# MLX90393SLW.net
KiCad netlist of a schematic drawn in Altium Designer
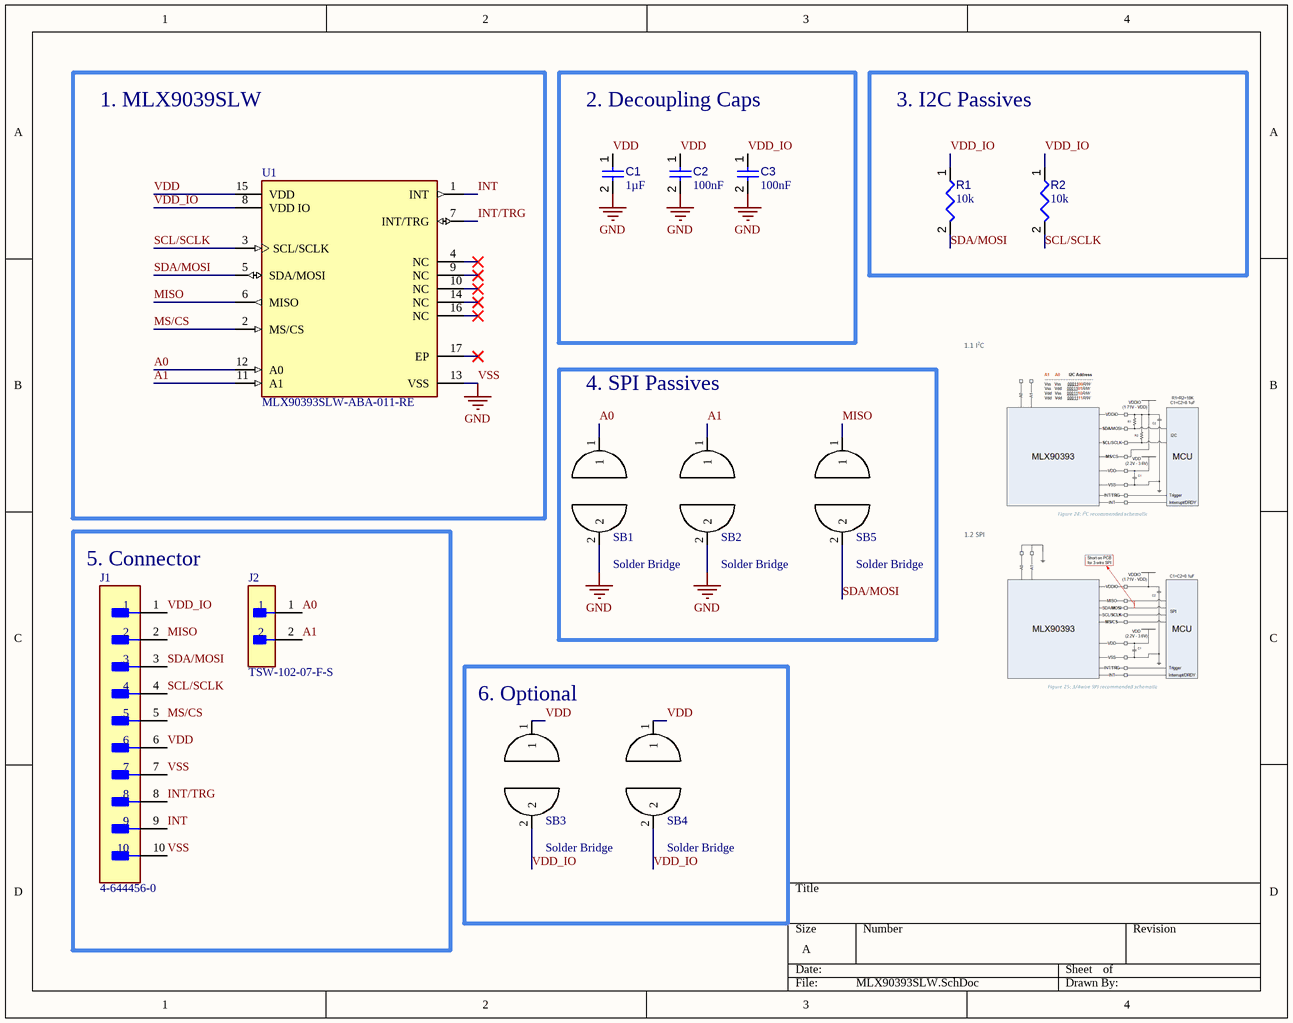
[diagram p0: MLX90393SLW.SchDoc]

(export (version "E")
  (design (tool "Eeschema 10.0.6"))
  (components
    (comp (ref "C1")
      (value "1µF")
      (footprint "CAPC0402(1005)60_L")
      (description "Chip Capacitor, 1µF +/-20%, 10V, 0402, Thickness 0.6 mm")
      (fields (field (name "TOLERANCE") "10%") (field (name "Comment") "Capacitor 1µF +/-20% 10V 0402"))
      (libsource (lib "SUBC") (part "CAP-NP-2"))
    )
    (comp (ref "C2")
      (value "100nF")
      (footprint "CAPC0402(1005)60_L")
      (description "Chip Capacitor, 100nF +/-20%, 25V, 0402, Thickness 0.6 mm")
      (fields (field (name "TOLERANCE") "10%") (field (name "Comment") "Capacitor 100nF +/-20% 25V 0402"))
      (libsource (lib "SUBC") (part "CAP-NP-2"))
    )
    (comp (ref "C3")
      (value "100nF")
      (footprint "CAPC0402(1005)60_L")
      (description "Chip Capacitor, 100nF +/-20%, 25V, 0402, Thickness 0.6 mm")
      (fields (field (name "TOLERANCE") "10%") (field (name "Comment") "Capacitor 100nF +/-20% 25V 0402"))
      (libsource (lib "SUBC") (part "CAP-NP-2"))
    )
    (comp (ref "J1")
      (value "4-644456-0")
      (footprint "FP-4-644456-0-MFG")
      (description "Conn Unshrouded Header HDR 10 POS 2.54mm Solder ST Top Entry Thru-Hole Bag/Box")
      (libsource (lib "SUBC") (part "aee40dc8b284c03a16094555aa210be"))
    )
    (comp (ref "J2")
      (value "TSW-102-07-F-S")
      (footprint "FP-TSW-102-07-F-S-MFG")
      (description "Conn Unshrouded Header HDR 2 POS 2.54mm Solder ST Top Entry Thru-Hole Bag")
      (libsource (lib "SUBC") (part "3bc925449376181038e59eaffc5286c"))
    )
    (comp (ref "R1")
      (value "10k")
      (footprint "RESC1608X55X25ML10T15")
      (description "Chip Resistor, 10 KOhm, +/- 1%, 01 W, -55 to 155 degC, 0603 (1608 Metric)")
      (fields (field (name "POWER") "100mW") (field (name "TOLERANCE") "1%"))
      (libsource (lib "SUBC") (part "RES-2"))
    )
    (comp (ref "R2")
      (value "10k")
      (footprint "RESC1608X55X25ML10T15")
      (description "Chip Resistor, 10 KOhm, +/- 1%, 01 W, -55 to 155 degC, 0603 (1608 Metric)")
      (fields (field (name "POWER") "100mW") (field (name "TOLERANCE") "1%"))
      (libsource (lib "SUBC") (part "RES-2"))
    )
    (comp (ref "SB1")
      (value "Solder Bridge")
      (footprint "Solder Bridge-Footprint-1")
      (description "Solder Bridge 10mil gap 6mil short")
      (libsource (lib "SUBC") (part "Solder Bridge-Symbol-1"))
    )
    (comp (ref "SB2")
      (value "Solder Bridge")
      (footprint "Solder Bridge-Footprint-1")
      (description "Solder Bridge 10mil gap 6mil short")
      (libsource (lib "SUBC") (part "Solder Bridge-Symbol-1"))
    )
    (comp (ref "SB3")
      (value "Solder Bridge")
      (footprint "Solder Bridge-Footprint-1")
      (description "Solder Bridge 10mil gap 6mil short")
      (libsource (lib "SUBC") (part "Solder Bridge-Symbol-1"))
    )
    (comp (ref "SB4")
      (value "Solder Bridge")
      (footprint "Solder Bridge-Footprint-1")
      (description "Solder Bridge 10mil gap 6mil short")
      (libsource (lib "SUBC") (part "Solder Bridge-Symbol-1"))
    )
    (comp (ref "SB5")
      (value "Solder Bridge")
      (footprint "Solder Bridge-Footprint-1")
      (description "Solder Bridge 10mil gap 6mil short")
      (libsource (lib "SUBC") (part "Solder Bridge-Symbol-1"))
    )
    (comp (ref "U1")
      (value "MLX90393SLW-ABA-011-RE")
      (footprint "FP-MLX90393SLW-ABA-011-RE-IPC_B")
      (description "Triaxis® Magnetic node - Micropower Magnetometer ft. SPI/I2C Output - I2C_addres")
      (libsource (lib "SUBC") (part "7beef37ec6f4d1a785de8af668c35a3"))
    )
  )
  (nets
    (net (code "1") (name "/A0") (class "Default")
      (node (ref "J2") (pin "1") (pinfunction "1_1") (pintype "passive"))
      (node (ref "SB1") (pin "1") (pinfunction "1_1") (pintype "passive"))
      (node (ref "U1") (pin "12") (pinfunction "A0_12") (pintype "input"))
    )
    (net (code "2") (name "/A1") (class "Default")
      (node (ref "J2") (pin "2") (pinfunction "2_2") (pintype "passive"))
      (node (ref "SB2") (pin "1") (pinfunction "1_1") (pintype "passive"))
      (node (ref "U1") (pin "11") (pinfunction "A1_11") (pintype "input"))
    )
    (net (code "3") (name "/INT") (class "Default")
      (node (ref "J1") (pin "9") (pinfunction "9_9") (pintype "passive"))
      (node (ref "U1") (pin "1") (pinfunction "INT_1") (pintype "output"))
    )
    (net (code "4") (name "/INT{slash}TRG") (class "Default")
      (node (ref "J1") (pin "8") (pinfunction "8_8") (pintype "passive"))
      (node (ref "U1") (pin "7") (pinfunction "INT/TRG_7") (pintype "bidirectional"))
    )
    (net (code "5") (name "/MISO") (class "Default")
      (node (ref "J1") (pin "2") (pinfunction "2_2") (pintype "passive"))
      (node (ref "SB5") (pin "1") (pinfunction "1_1") (pintype "passive"))
      (node (ref "U1") (pin "6") (pinfunction "MISO_6") (pintype "output"))
    )
    (net (code "6") (name "/MS{slash}CS") (class "Default")
      (node (ref "J1") (pin "5") (pinfunction "5_5") (pintype "passive"))
      (node (ref "U1") (pin "2") (pinfunction "MS/CS_2") (pintype "input"))
    )
    (net (code "7") (name "/SCL{slash}SCLK") (class "Default")
      (node (ref "J1") (pin "4") (pinfunction "4_4") (pintype "passive"))
      (node (ref "R2") (pin "2") (pinfunction "2_2") (pintype "passive"))
      (node (ref "U1") (pin "3") (pinfunction "SCL/SCLK_3") (pintype "input"))
    )
    (net (code "8") (name "/SDA{slash}MOSI") (class "Default")
      (node (ref "J1") (pin "3") (pinfunction "3_3") (pintype "passive"))
      (node (ref "R1") (pin "2") (pinfunction "2_2") (pintype "passive"))
      (node (ref "SB5") (pin "2") (pinfunction "2_2") (pintype "passive"))
      (node (ref "U1") (pin "5") (pinfunction "SDA/MOSI_5") (pintype "bidirectional"))
    )
    (net (code "9") (name "/VDD") (class "Default")
      (node (ref "C1") (pin "1") (pinfunction "1_1") (pintype "passive"))
      (node (ref "C2") (pin "1") (pinfunction "1_1") (pintype "passive"))
      (node (ref "J1") (pin "6") (pinfunction "6_6") (pintype "passive"))
      (node (ref "SB3") (pin "1") (pinfunction "1_1") (pintype "passive"))
      (node (ref "SB4") (pin "1") (pinfunction "1_1") (pintype "passive"))
      (node (ref "U1") (pin "15") (pinfunction "VDD_15") (pintype "power_in"))
    )
    (net (code "10") (name "/VDD_IO") (class "Default")
      (node (ref "C3") (pin "1") (pinfunction "1_1") (pintype "passive"))
      (node (ref "J1") (pin "1") (pinfunction "1_1") (pintype "passive"))
      (node (ref "R1") (pin "1") (pinfunction "1_1") (pintype "passive"))
      (node (ref "R2") (pin "1") (pinfunction "1_1") (pintype "passive"))
      (node (ref "SB3") (pin "2") (pinfunction "2_2") (pintype "passive"))
      (node (ref "SB4") (pin "2") (pinfunction "2_2") (pintype "passive"))
      (node (ref "U1") (pin "8") (pinfunction "VDD_IO_8") (pintype "power_in"))
    )
    (net (code "11") (name "GND") (class "Default")
      (node (ref "C1") (pin "2") (pinfunction "2_2") (pintype "passive"))
      (node (ref "C2") (pin "2") (pinfunction "2_2") (pintype "passive"))
      (node (ref "C3") (pin "2") (pinfunction "2_2") (pintype "passive"))
      (node (ref "J1") (pin "10") (pinfunction "10_10") (pintype "passive"))
      (node (ref "J1") (pin "7") (pinfunction "7_7") (pintype "passive"))
      (node (ref "SB1") (pin "2") (pinfunction "2_2") (pintype "passive"))
      (node (ref "SB2") (pin "2") (pinfunction "2_2") (pintype "passive"))
      (node (ref "U1") (pin "13") (pinfunction "VSS_13") (pintype "power_in"))
    )
    (net (code "12") (name "unconnected-(U1-EP-Pad17)") (class "Default")
      (node (ref "U1") (pin "17") (pinfunction "EP_17") (pintype "passive+no_connect"))
    )
    (net (code "13") (name "unconnected-(U1-NC-Pad4)") (class "Default")
      (node (ref "U1") (pin "4") (pinfunction "NC_4") (pintype "passive+no_connect"))
    )
    (net (code "14") (name "unconnected-(U1-NC-Pad9)") (class "Default")
      (node (ref "U1") (pin "9") (pinfunction "NC_9") (pintype "passive+no_connect"))
    )
    (net (code "15") (name "unconnected-(U1-NC-Pad10)") (class "Default")
      (node (ref "U1") (pin "10") (pinfunction "NC_10") (pintype "passive+no_connect"))
    )
    (net (code "16") (name "unconnected-(U1-NC-Pad14)") (class "Default")
      (node (ref "U1") (pin "14") (pinfunction "NC_14") (pintype "passive+no_connect"))
    )
    (net (code "17") (name "unconnected-(U1-NC-Pad16)") (class "Default")
      (node (ref "U1") (pin "16") (pinfunction "NC_16") (pintype "passive+no_connect"))
    )
  )
)
